# esp_battery.net
KiCad netlist of a schematic drawn in EAGLE
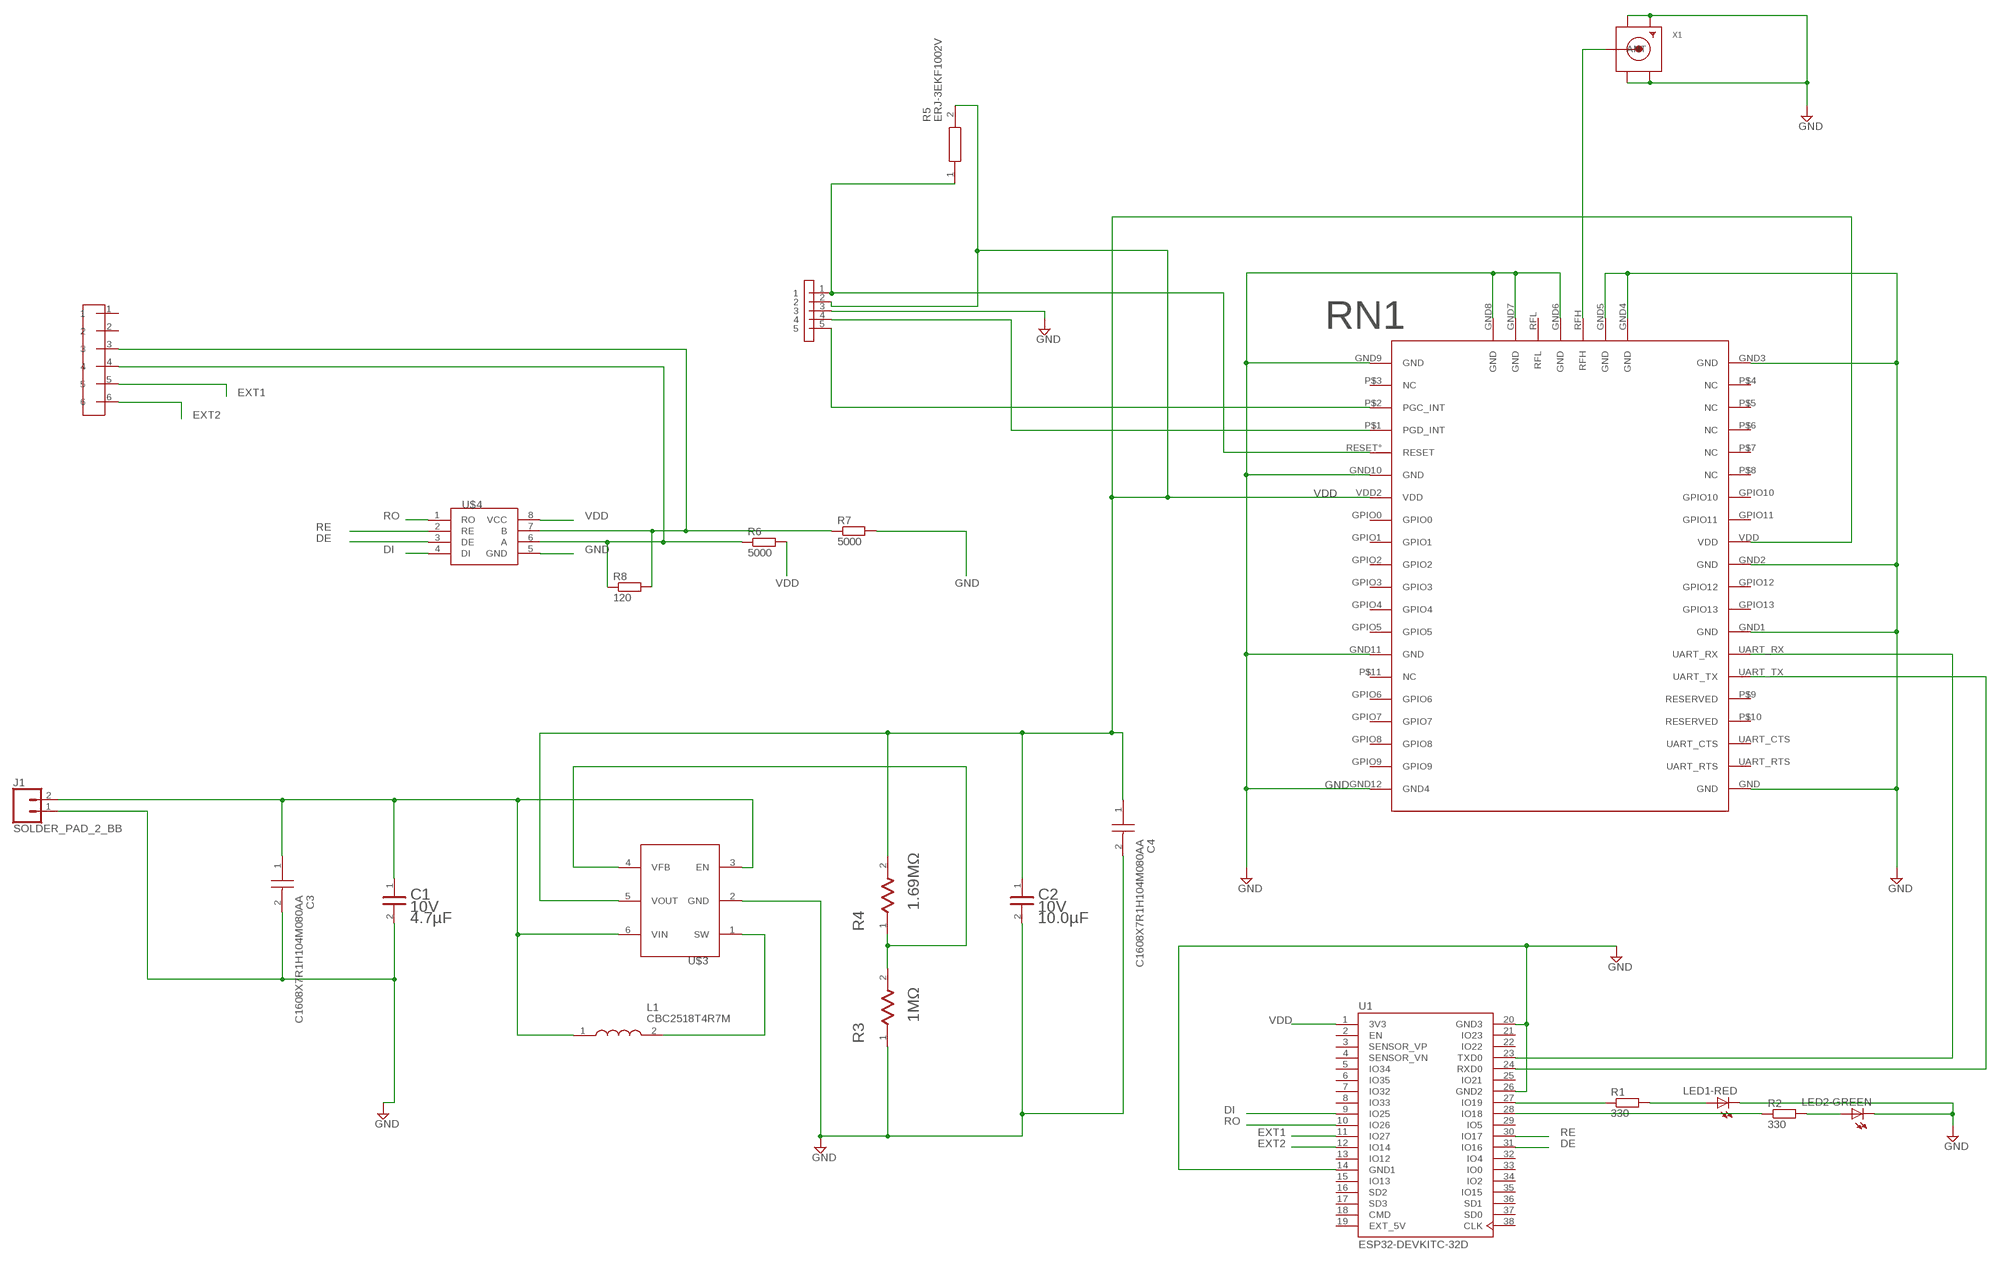
[diagram p0: schematic, sheet 1]

(export (version "E")
  (design (tool "Eeschema 10.0.6"))
  (components
    (comp (ref "C1")
      (value "KEMET_C0603C475K8PACTUKEMET_C0603C475K8PACTU_0_0")
      (footprint "eagle-import:KEMET_C0603C475K8PACTU_0")
      (fields
        (field (name "DIGIKEY_PART_NUMBER") "399-5503-1-ND")
        (field (name "MF") "Kemet")
        (field (name "MOUSER_PART_NUMBER") "80-C0603C475K8P")
      )
      (libsource (lib "eagle-import") (part "KEMET_C0603C475K8PACTUKEMET_C0603C475K8PACTU_0_0"))
    )
    (comp (ref "C2")
      (value "TDK_C1608X5R1A106M080ACTDK_C1608X5R1A106M080AC_0_0")
      (footprint "eagle-import:TDK_C1608X5R1A106M080AC_0")
      (fields
        (field (name "DIGIKEY_PART_NUMBER") "445-6853-1-ND")
        (field (name "MF") "TDK")
        (field (name "MOUSER_PART_NUMBER") "810-C1608X5R1A106M")
      )
      (libsource (lib "eagle-import") (part "TDK_C1608X5R1A106M080ACTDK_C1608X5R1A106M080AC_0_0"))
    )
    (comp (ref "C3")
      (value "C1608X7R1H104M080AA")
      (footprint "eagle-import:CAPC1608X80N")
      (fields (field (name "MOUSER_PART_NUMBER") "810-C1608X7R1H104M"))
      (libsource (lib "eagle-import") (part "C1608X7R1H104M080AA"))
    )
    (comp (ref "C4")
      (value "C1608X7R1H104M080AA")
      (footprint "eagle-import:CAPC1608X80N")
      (fields (field (name "MOUSER_PART_NUMBER") "810-C1608X7R1H104M"))
      (libsource (lib "eagle-import") (part "C1608X7R1H104M080AA"))
    )
    (comp (ref "J1")
      (value "SOLDER_PAD_2_BB")
      (footprint "eagle-import:SOLDER_PAD_2")
      (libsource (lib "eagle-import") (part "SOLDER_PAD_2_BB"))
    )
    (comp (ref "L1")
      (value "CBC2518T4R7M")
      (footprint "eagle-import:INDC2518X200N")
      (fields (field (name "MOUSER_PART_NUMBER") "963-CBC2518T4R7M"))
      (libsource (lib "eagle-import") (part "CBC2518T4R7M"))
    )
    (comp (ref "LED1-RED")
      (value "LEDCHIP-LED0603")
      (footprint "eagle-import:CHIP-LED0603")
      (libsource (lib "eagle-import") (part "LEDCHIP-LED0603"))
    )
    (comp (ref "LED2-GREEN")
      (value "LEDCHIP-LED0603")
      (footprint "eagle-import:CHIP-LED0603")
      (libsource (lib "eagle-import") (part "LEDCHIP-LED0603"))
    )
    (comp (ref "R1")
      (value "330")
      (footprint "eagle-import:R0603")
      (libsource (lib "eagle-import") (part "R-EU_R0603"))
    )
    (comp (ref "R2")
      (value "330")
      (footprint "eagle-import:R0603")
      (libsource (lib "eagle-import") (part "R-EU_R0603"))
    )
    (comp (ref "R3")
      (value "STACKPOLE_RMCF0603FT1M00STACKPOLE_RMCF0603FT1M00_0_1")
      (footprint "eagle-import:STACKPOLE_RMCF0603FT1M00_1")
      (fields
        (field (name "APPROVED_ALTERNATE_PART_NUMBER") "541-1.00HHCT-ND")
        (field (name "DIGIKEY_PART_NUMBER") "RMCF0603FT1M00-ND")
        (field (name "MF") "Stackpole")
      )
      (libsource (lib "eagle-import") (part "STACKPOLE_RMCF0603FT1M00STACKPOLE_RMCF0603FT1M00_0_1"))
    )
    (comp (ref "R4")
      (value "VISHAY_CRCW06031M69FKEAVISHAY_CRCW06031M69FKEA_0_1")
      (footprint "eagle-import:VISHAY_CRCW06031M69FKEA_1")
      (fields
        (field (name "APPROVED_ALTERNATE_PART_NUMBER") "541-1.00HHCT-ND")
        (field (name "DIGIKEY_PART_NUMBER") "541-1.69MHTR-ND")
        (field (name "MF") "Vishay")
      )
      (libsource (lib "eagle-import") (part "VISHAY_CRCW06031M69FKEAVISHAY_CRCW06031M69FKEA_0_1"))
    )
    (comp (ref "R5")
      (value "ERJ-3EKF1002V")
      (footprint "eagle-import:RESC1608X55N")
      (fields (field (name "MOUSER_PART_NUMBER") "667-ERJ-3EKF1002V"))
      (libsource (lib "eagle-import") (part "ERJ-3EKF1002V"))
    )
    (comp (ref "R6")
      (value "5000")
      (footprint "eagle-import:R0805")
      (libsource (lib "eagle-import") (part "R-EU_R0805"))
    )
    (comp (ref "R7")
      (value "5000")
      (footprint "eagle-import:R0805")
      (libsource (lib "eagle-import") (part "R-EU_R0805"))
    )
    (comp (ref "R8")
      (value "120")
      (footprint "eagle-import:R0805")
      (libsource (lib "eagle-import") (part "R-EU_R0805"))
    )
    (comp (ref "RN1")
      (value "NEW_RN2483")
      (footprint "eagle-import:NEW_RN2483")
      (libsource (lib "eagle-import") (part "NEW_RN2483"))
    )
    (comp (ref "U$1")
      (value "CONNECTOR62")
      (footprint "eagle-import:CONNECTOR6")
      (libsource (lib "eagle-import") (part "CONNECTOR62"))
    )
    (comp (ref "U$2")
      (value "ICSP52")
      (footprint "eagle-import:ICSP")
      (libsource (lib "eagle-import") (part "ICSP52"))
    )
    (comp (ref "U$3")
      (value "MCP16252")
      (footprint "eagle-import:MCP16252")
      (libsource (lib "eagle-import") (part "MCP16252"))
    )
    (comp (ref "U$4")
      (value "AMD3485E")
      (footprint "eagle-import:AMD3485E")
      (libsource (lib "eagle-import") (part "AMD3485E"))
    )
    (comp (ref "U1")
      (value "ESP32-DEVKITC-32D")
      (footprint "eagle-import:MODULE_ESP32-DEVKITC-32D")
      (fields (field (name "MF") "Espressif Systems"))
      (libsource (lib "eagle-import") (part "ESP32-DEVKITC-32D"))
    )
    (comp (ref "X1")
      (value "SMACONNECTOR_EDGE")
      (footprint "eagle-import:SMA_EDGELAUNCH")
      (libsource (lib "eagle-import") (part "SMACONNECTOR_EDGE"))
    )
  )
  (nets
    (net (code "1") (name "/DE") (class "Default")
      (node (ref "U$4") (pin "3") (pinfunction "DE_3") (pintype "bidirectional"))
      (node (ref "U1") (pin "31") (pinfunction "IO16_31") (pintype "bidirectional"))
    )
    (net (code "2") (name "/DI") (class "Default")
      (node (ref "U$4") (pin "4") (pinfunction "DI_4") (pintype "bidirectional"))
      (node (ref "U1") (pin "9") (pinfunction "IO25_9") (pintype "bidirectional"))
    )
    (net (code "3") (name "/EXT1") (class "Default")
      (node (ref "U$1") (pin "5") (pinfunction "5_5") (pintype "bidirectional"))
      (node (ref "U1") (pin "11") (pinfunction "IO27_11") (pintype "bidirectional"))
    )
    (net (code "4") (name "/EXT2") (class "Default")
      (node (ref "U$1") (pin "6") (pinfunction "6_6") (pintype "bidirectional"))
      (node (ref "U1") (pin "12") (pinfunction "IO14_12") (pintype "bidirectional"))
    )
    (net (code "5") (name "/EXT_5V") (class "Default")
      (node (ref "U1") (pin "19") (pinfunction "EXT_5V_19") (pintype "power_in"))
    )
    (net (code "6") (name "/RE") (class "Default")
      (node (ref "U$4") (pin "2") (pinfunction "RE_2") (pintype "bidirectional"))
      (node (ref "U1") (pin "30") (pinfunction "IO17_30") (pintype "bidirectional"))
    )
    (net (code "7") (name "/RO") (class "Default")
      (node (ref "U$4") (pin "1") (pinfunction "RO_1") (pintype "bidirectional"))
      (node (ref "U1") (pin "10") (pinfunction "IO26_10") (pintype "bidirectional"))
    )
    (net (code "8") (name "/VDD") (class "Default")
      (node (ref "C2") (pin "1") (pinfunction "1_1") (pintype "bidirectional"))
      (node (ref "C4") (pin "1") (pinfunction "1_1") (pintype "bidirectional"))
      (node (ref "R4") (pin "2") (pinfunction "2_2") (pintype "passive"))
      (node (ref "R5") (pin "2") (pinfunction "2_2") (pintype "bidirectional"))
      (node (ref "R6") (pin "2") (pinfunction "2_2") (pintype "passive"))
      (node (ref "RN1") (pin "VDD") (pinfunction "VDD_VDD") (pintype "bidirectional"))
      (node (ref "RN1") (pin "VDD2") (pinfunction "VDD_VDD2") (pintype "bidirectional"))
      (node (ref "U$2") (pin "2") (pinfunction "2_2") (pintype "bidirectional"))
      (node (ref "U$3") (pin "5") (pinfunction "VOUT_5") (pintype "bidirectional"))
      (node (ref "U$4") (pin "8") (pinfunction "VCC_8") (pintype "bidirectional"))
      (node (ref "U1") (pin "1") (pinfunction "3V3_1") (pintype "power_in"))
    )
    (net (code "9") (name "GND") (class "Default")
      (node (ref "C1") (pin "2") (pinfunction "2_2") (pintype "bidirectional"))
      (node (ref "C2") (pin "2") (pinfunction "2_2") (pintype "bidirectional"))
      (node (ref "C3") (pin "2") (pinfunction "2_2") (pintype "bidirectional"))
      (node (ref "C4") (pin "2") (pinfunction "2_2") (pintype "bidirectional"))
      (node (ref "J1") (pin "1") (pinfunction "1_1") (pintype "passive"))
      (node (ref "LED1-RED") (pin "C") (pinfunction "C_C") (pintype "passive"))
      (node (ref "LED2-GREEN") (pin "C") (pinfunction "C_C") (pintype "passive"))
      (node (ref "R3") (pin "1") (pinfunction "1_1") (pintype "passive"))
      (node (ref "R7") (pin "2") (pinfunction "2_2") (pintype "passive"))
      (node (ref "RN1") (pin "GND") (pinfunction "GND_GND") (pintype "bidirectional"))
      (node (ref "RN1") (pin "GND1") (pinfunction "GND_GND1") (pintype "bidirectional"))
      (node (ref "RN1") (pin "GND10") (pinfunction "GND_GND10") (pintype "bidirectional"))
      (node (ref "RN1") (pin "GND11") (pinfunction "GND_GND11") (pintype "bidirectional"))
      (node (ref "RN1") (pin "GND12") (pinfunction "GND4_GND12") (pintype "bidirectional"))
      (node (ref "RN1") (pin "GND2") (pinfunction "GND_GND2") (pintype "bidirectional"))
      (node (ref "RN1") (pin "GND3") (pinfunction "GND_GND3") (pintype "bidirectional"))
      (node (ref "RN1") (pin "GND4") (pinfunction "GND_GND4") (pintype "bidirectional"))
      (node (ref "RN1") (pin "GND5") (pinfunction "GND_GND5") (pintype "bidirectional"))
      (node (ref "RN1") (pin "GND6") (pinfunction "GND_GND6") (pintype "bidirectional"))
      (node (ref "RN1") (pin "GND7") (pinfunction "GND_GND7") (pintype "bidirectional"))
      (node (ref "RN1") (pin "GND8") (pinfunction "GND_GND8") (pintype "bidirectional"))
      (node (ref "RN1") (pin "GND9") (pinfunction "GND_GND9") (pintype "bidirectional"))
      (node (ref "U$2") (pin "3") (pinfunction "3_3") (pintype "bidirectional"))
      (node (ref "U$3") (pin "2") (pinfunction "GND_2") (pintype "bidirectional"))
      (node (ref "U$4") (pin "5") (pinfunction "GND_5") (pintype "bidirectional"))
      (node (ref "U1") (pin "14") (pinfunction "GND1_14") (pintype "power_in"))
      (node (ref "U1") (pin "20") (pinfunction "GND3_20") (pintype "power_in"))
      (node (ref "U1") (pin "26") (pinfunction "GND2_26") (pintype "power_in"))
      (node (ref "X1") (pin "GND@1") (pinfunction "GND4_GND@1") (pintype "power_in"))
      (node (ref "X1") (pin "GND@2") (pinfunction "GND3_GND@2") (pintype "power_in"))
      (node (ref "X1") (pin "GND@3") (pinfunction "GND2_GND@3") (pintype "power_in"))
      (node (ref "X1") (pin "GND@4") (pinfunction "GND1_GND@4") (pintype "power_in"))
    )
    (net (code "10") (name "Net-(LED1-RED-PadA)") (class "Default")
      (node (ref "LED1-RED") (pin "A") (pinfunction "A_A") (pintype "passive"))
      (node (ref "R1") (pin "2") (pinfunction "2_2") (pintype "passive"))
    )
    (net (code "11") (name "Net-(LED2-GREEN-PadA)") (class "Default")
      (node (ref "LED2-GREEN") (pin "A") (pinfunction "A_A") (pintype "passive"))
      (node (ref "R2") (pin "2") (pinfunction "2_2") (pintype "passive"))
    )
    (net (code "12") (name "Net-(RN1-PGC_INT)") (class "Default")
      (node (ref "RN1") (pin "P$2") (pinfunction "PGC_INT_P$2") (pintype "bidirectional"))
      (node (ref "U$2") (pin "5") (pinfunction "5_5") (pintype "bidirectional"))
    )
    (net (code "13") (name "Net-(RN1-PGD_INT)") (class "Default")
      (node (ref "RN1") (pin "P$1") (pinfunction "PGD_INT_P$1") (pintype "bidirectional"))
      (node (ref "U$2") (pin "4") (pinfunction "4_4") (pintype "bidirectional"))
    )
    (net (code "14") (name "Net-(RN1-RESET)") (class "Default")
      (node (ref "R5") (pin "1") (pinfunction "1_1") (pintype "bidirectional"))
      (node (ref "RN1") (pin "RESET°") (pinfunction "RESET_RESET°") (pintype "bidirectional"))
      (node (ref "U$2") (pin "1") (pinfunction "1_1") (pintype "bidirectional"))
    )
    (net (code "15") (name "Net-(U$3-EN)") (class "Default")
      (node (ref "C1") (pin "1") (pinfunction "1_1") (pintype "bidirectional"))
      (node (ref "C3") (pin "1") (pinfunction "1_1") (pintype "bidirectional"))
      (node (ref "J1") (pin "2") (pinfunction "2_2") (pintype "passive"))
      (node (ref "L1") (pin "1") (pinfunction "1_1") (pintype "bidirectional"))
      (node (ref "U$3") (pin "3") (pinfunction "EN_3") (pintype "bidirectional"))
      (node (ref "U$3") (pin "6") (pinfunction "VIN_6") (pintype "bidirectional"))
    )
    (net (code "16") (name "Net-(U$3-SW)") (class "Default")
      (node (ref "L1") (pin "2") (pinfunction "2_2") (pintype "bidirectional"))
      (node (ref "U$3") (pin "1") (pinfunction "SW_1") (pintype "bidirectional"))
    )
    (net (code "17") (name "Net-(U$3-VFB)") (class "Default")
      (node (ref "R3") (pin "2") (pinfunction "2_2") (pintype "passive"))
      (node (ref "R4") (pin "1") (pinfunction "1_1") (pintype "passive"))
      (node (ref "U$3") (pin "4") (pinfunction "VFB_4") (pintype "bidirectional"))
    )
    (net (code "18") (name "Net-(U$4-A)") (class "Default")
      (node (ref "R6") (pin "1") (pinfunction "1_1") (pintype "passive"))
      (node (ref "R8") (pin "1") (pinfunction "1_1") (pintype "passive"))
      (node (ref "U$1") (pin "4") (pinfunction "4_4") (pintype "bidirectional"))
      (node (ref "U$4") (pin "6") (pinfunction "A_6") (pintype "bidirectional"))
    )
    (net (code "19") (name "Net-(U$4-B)") (class "Default")
      (node (ref "R7") (pin "1") (pinfunction "1_1") (pintype "passive"))
      (node (ref "R8") (pin "2") (pinfunction "2_2") (pintype "passive"))
      (node (ref "U$1") (pin "3") (pinfunction "3_3") (pintype "bidirectional"))
      (node (ref "U$4") (pin "7") (pinfunction "B_7") (pintype "bidirectional"))
    )
    (net (code "20") (name "Net-(U1-IO18)") (class "Default")
      (node (ref "R2") (pin "1") (pinfunction "1_1") (pintype "passive"))
      (node (ref "U1") (pin "28") (pinfunction "IO18_28") (pintype "bidirectional"))
    )
    (net (code "21") (name "Net-(U1-IO19)") (class "Default")
      (node (ref "R1") (pin "1") (pinfunction "1_1") (pintype "passive"))
      (node (ref "U1") (pin "27") (pinfunction "IO19_27") (pintype "bidirectional"))
    )
    (net (code "22") (name "Net-(U1-RXD0)") (class "Default")
      (node (ref "RN1") (pin "UART_TX") (pinfunction "UART_TX_UART_TX") (pintype "bidirectional"))
      (node (ref "U1") (pin "24") (pinfunction "RXD0_24") (pintype "input"))
    )
    (net (code "23") (name "Net-(U1-TXD0)") (class "Default")
      (node (ref "RN1") (pin "UART_RX") (pinfunction "UART_RX_UART_RX") (pintype "bidirectional"))
      (node (ref "U1") (pin "23") (pinfunction "TXD0_23") (pintype "output"))
    )
    (net (code "24") (name "Net-(X1-ANT)") (class "Default")
      (node (ref "RN1") (pin "RFH") (pinfunction "RFH_RFH") (pintype "bidirectional"))
      (node (ref "X1") (pin "P") (pinfunction "ANT_P") (pintype "bidirectional"))
    )
    (net (code "25") (name "unconnected-(RN1-NC-PadP$3)") (class "Default")
      (node (ref "RN1") (pin "P$3") (pinfunction "NC_P$3") (pintype "bidirectional"))
    )
    (net (code "26") (name "unconnected-(RN1-NC-PadP$4)") (class "Default")
      (node (ref "RN1") (pin "P$4") (pinfunction "NC_P$4") (pintype "bidirectional"))
    )
    (net (code "27") (name "unconnected-(RN1-NC-PadP$5)") (class "Default")
      (node (ref "RN1") (pin "P$5") (pinfunction "NC_P$5") (pintype "bidirectional"))
    )
    (net (code "28") (name "unconnected-(RN1-NC-PadP$6)") (class "Default")
      (node (ref "RN1") (pin "P$6") (pinfunction "NC_P$6") (pintype "bidirectional"))
    )
    (net (code "29") (name "unconnected-(RN1-NC-PadP$7)") (class "Default")
      (node (ref "RN1") (pin "P$7") (pinfunction "NC_P$7") (pintype "bidirectional"))
    )
    (net (code "30") (name "unconnected-(RN1-NC-PadP$8)") (class "Default")
      (node (ref "RN1") (pin "P$8") (pinfunction "NC_P$8") (pintype "bidirectional"))
    )
    (net (code "31") (name "unconnected-(RN1-NC-PadP$11)") (class "Default")
      (node (ref "RN1") (pin "P$11") (pinfunction "NC_P$11") (pintype "bidirectional"))
    )
    (net (code "32") (name "unconnected-(RN1-PadGPIO0)") (class "Default")
      (node (ref "RN1") (pin "GPIO0") (pinfunction "GPIO0_GPIO0") (pintype "bidirectional"))
    )
    (net (code "33") (name "unconnected-(RN1-PadGPIO1)") (class "Default")
      (node (ref "RN1") (pin "GPIO1") (pinfunction "GPIO1_GPIO1") (pintype "bidirectional"))
    )
    (net (code "34") (name "unconnected-(RN1-PadGPIO2)") (class "Default")
      (node (ref "RN1") (pin "GPIO2") (pinfunction "GPIO2_GPIO2") (pintype "bidirectional"))
    )
    (net (code "35") (name "unconnected-(RN1-PadGPIO3)") (class "Default")
      (node (ref "RN1") (pin "GPIO3") (pinfunction "GPIO3_GPIO3") (pintype "bidirectional"))
    )
    (net (code "36") (name "unconnected-(RN1-PadGPIO4)") (class "Default")
      (node (ref "RN1") (pin "GPIO4") (pinfunction "GPIO4_GPIO4") (pintype "bidirectional"))
    )
    (net (code "37") (name "unconnected-(RN1-PadGPIO5)") (class "Default")
      (node (ref "RN1") (pin "GPIO5") (pinfunction "GPIO5_GPIO5") (pintype "bidirectional"))
    )
    (net (code "38") (name "unconnected-(RN1-PadGPIO6)") (class "Default")
      (node (ref "RN1") (pin "GPIO6") (pinfunction "GPIO6_GPIO6") (pintype "bidirectional"))
    )
    (net (code "39") (name "unconnected-(RN1-PadGPIO7)") (class "Default")
      (node (ref "RN1") (pin "GPIO7") (pinfunction "GPIO7_GPIO7") (pintype "bidirectional"))
    )
    (net (code "40") (name "unconnected-(RN1-PadGPIO8)") (class "Default")
      (node (ref "RN1") (pin "GPIO8") (pinfunction "GPIO8_GPIO8") (pintype "bidirectional"))
    )
    (net (code "41") (name "unconnected-(RN1-PadGPIO9)") (class "Default")
      (node (ref "RN1") (pin "GPIO9") (pinfunction "GPIO9_GPIO9") (pintype "bidirectional"))
    )
    (net (code "42") (name "unconnected-(RN1-PadGPIO10)") (class "Default")
      (node (ref "RN1") (pin "GPIO10") (pinfunction "GPIO10_GPIO10") (pintype "bidirectional"))
    )
    (net (code "43") (name "unconnected-(RN1-PadGPIO11)") (class "Default")
      (node (ref "RN1") (pin "GPIO11") (pinfunction "GPIO11_GPIO11") (pintype "bidirectional"))
    )
    (net (code "44") (name "unconnected-(RN1-PadGPIO12)") (class "Default")
      (node (ref "RN1") (pin "GPIO12") (pinfunction "GPIO12_GPIO12") (pintype "bidirectional"))
    )
    (net (code "45") (name "unconnected-(RN1-PadGPIO13)") (class "Default")
      (node (ref "RN1") (pin "GPIO13") (pinfunction "GPIO13_GPIO13") (pintype "bidirectional"))
    )
    (net (code "46") (name "unconnected-(RN1-PadRFL)") (class "Default")
      (node (ref "RN1") (pin "RFL") (pinfunction "RFL_RFL") (pintype "bidirectional"))
    )
    (net (code "47") (name "unconnected-(RN1-PadUART_CTS)") (class "Default")
      (node (ref "RN1") (pin "UART_CTS") (pinfunction "UART_CTS_UART_CTS") (pintype "bidirectional"))
    )
    (net (code "48") (name "unconnected-(RN1-PadUART_RTS)") (class "Default")
      (node (ref "RN1") (pin "UART_RTS") (pinfunction "UART_RTS_UART_RTS") (pintype "bidirectional"))
    )
    (net (code "49") (name "unconnected-(RN1-RESERVED-PadP$9)") (class "Default")
      (node (ref "RN1") (pin "P$9") (pinfunction "RESERVED_P$9") (pintype "bidirectional"))
    )
    (net (code "50") (name "unconnected-(RN1-RESERVED-PadP$10)") (class "Default")
      (node (ref "RN1") (pin "P$10") (pinfunction "RESERVED_P$10") (pintype "bidirectional"))
    )
    (net (code "51") (name "unconnected-(U$1-Pad1)") (class "Default")
      (node (ref "U$1") (pin "1") (pinfunction "1_1") (pintype "bidirectional"))
    )
    (net (code "52") (name "unconnected-(U$1-Pad2)") (class "Default")
      (node (ref "U$1") (pin "2") (pinfunction "2_2") (pintype "bidirectional"))
    )
    (net (code "53") (name "unconnected-(U1-CLK-Pad38)") (class "Default")
      (node (ref "U1") (pin "38") (pinfunction "CLK_38") (pintype "input"))
    )
    (net (code "54") (name "unconnected-(U1-CMD-Pad18)") (class "Default")
      (node (ref "U1") (pin "18") (pinfunction "CMD_18") (pintype "bidirectional"))
    )
    (net (code "55") (name "unconnected-(U1-EN-Pad2)") (class "Default")
      (node (ref "U1") (pin "2") (pinfunction "EN_2") (pintype "input"))
    )
    (net (code "56") (name "unconnected-(U1-IO0-Pad33)") (class "Default")
      (node (ref "U1") (pin "33") (pinfunction "IO0_33") (pintype "bidirectional"))
    )
    (net (code "57") (name "unconnected-(U1-IO2-Pad34)") (class "Default")
      (node (ref "U1") (pin "34") (pinfunction "IO2_34") (pintype "bidirectional"))
    )
    (net (code "58") (name "unconnected-(U1-IO4-Pad32)") (class "Default")
      (node (ref "U1") (pin "32") (pinfunction "IO4_32") (pintype "bidirectional"))
    )
    (net (code "59") (name "unconnected-(U1-IO5-Pad29)") (class "Default")
      (node (ref "U1") (pin "29") (pinfunction "IO5_29") (pintype "bidirectional"))
    )
    (net (code "60") (name "unconnected-(U1-IO12-Pad13)") (class "Default")
      (node (ref "U1") (pin "13") (pinfunction "IO12_13") (pintype "bidirectional"))
    )
    (net (code "61") (name "unconnected-(U1-IO13-Pad15)") (class "Default")
      (node (ref "U1") (pin "15") (pinfunction "IO13_15") (pintype "bidirectional"))
    )
    (net (code "62") (name "unconnected-(U1-IO15-Pad35)") (class "Default")
      (node (ref "U1") (pin "35") (pinfunction "IO15_35") (pintype "bidirectional"))
    )
    (net (code "63") (name "unconnected-(U1-IO21-Pad25)") (class "Default")
      (node (ref "U1") (pin "25") (pinfunction "IO21_25") (pintype "bidirectional"))
    )
    (net (code "64") (name "unconnected-(U1-IO22-Pad22)") (class "Default")
      (node (ref "U1") (pin "22") (pinfunction "IO22_22") (pintype "bidirectional"))
    )
    (net (code "65") (name "unconnected-(U1-IO23-Pad21)") (class "Default")
      (node (ref "U1") (pin "21") (pinfunction "IO23_21") (pintype "bidirectional"))
    )
    (net (code "66") (name "unconnected-(U1-IO32-Pad7)") (class "Default")
      (node (ref "U1") (pin "7") (pinfunction "IO32_7") (pintype "bidirectional"))
    )
    (net (code "67") (name "unconnected-(U1-IO33-Pad8)") (class "Default")
      (node (ref "U1") (pin "8") (pinfunction "IO33_8") (pintype "bidirectional"))
    )
    (net (code "68") (name "unconnected-(U1-IO34-Pad5)") (class "Default")
      (node (ref "U1") (pin "5") (pinfunction "IO34_5") (pintype "bidirectional"))
    )
    (net (code "69") (name "unconnected-(U1-IO35-Pad6)") (class "Default")
      (node (ref "U1") (pin "6") (pinfunction "IO35_6") (pintype "bidirectional"))
    )
    (net (code "70") (name "unconnected-(U1-SD0-Pad37)") (class "Default")
      (node (ref "U1") (pin "37") (pinfunction "SD0_37") (pintype "bidirectional"))
    )
    (net (code "71") (name "unconnected-(U1-SD1-Pad36)") (class "Default")
      (node (ref "U1") (pin "36") (pinfunction "SD1_36") (pintype "bidirectional"))
    )
    (net (code "72") (name "unconnected-(U1-SD2-Pad16)") (class "Default")
      (node (ref "U1") (pin "16") (pinfunction "SD2_16") (pintype "bidirectional"))
    )
    (net (code "73") (name "unconnected-(U1-SD3-Pad17)") (class "Default")
      (node (ref "U1") (pin "17") (pinfunction "SD3_17") (pintype "bidirectional"))
    )
    (net (code "74") (name "unconnected-(U1-SENSOR_VN-Pad4)") (class "Default")
      (node (ref "U1") (pin "4") (pinfunction "SENSOR_VN_4") (pintype "input"))
    )
    (net (code "75") (name "unconnected-(U1-SENSOR_VP-Pad3)") (class "Default")
      (node (ref "U1") (pin "3") (pinfunction "SENSOR_VP_3") (pintype "input"))
    )
  )
)
